# PORT.net
KiCad netlist of a schematic drawn in Altium Designer
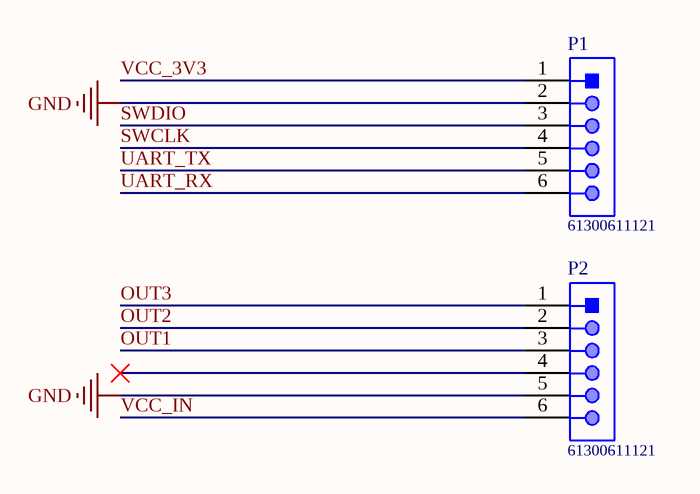
[diagram p0: PORT.SchDoc]

(export (version "E")
  (design (tool "Eeschema 10.0.6"))
  (components
    (comp (ref "P1")
      (value "61300611121")
      (footprint "61300611121")
      (description "THT Vertical Pin Header WR-PHD, Pitch 2.54 mm, Single Row, 6 pins")
      (fields (field (name "MANUFACTURER") "Wurth Elektronik") (field (name "PUBLISHER") "WurthElektronik"))
      (libsource (lib "Altium Content Vault") (part "WE-CN-1P-M-R6"))
    )
    (comp (ref "P2")
      (value "61300611121")
      (footprint "61300611121")
      (description "THT Vertical Pin Header WR-PHD, Pitch 2.54 mm, Single Row, 6 pins")
      (fields (field (name "MANUFACTURER") "Wurth Elektronik") (field (name "PUBLISHER") "WurthElektronik"))
      (libsource (lib "Altium Content Vault") (part "WE-CN-1P-M-R6"))
    )
  )
  (nets
    (net (code "1") (name "/OUT1") (class "Default")
      (node (ref "P2") (pin "3") (pinfunction "3_3") (pintype "passive"))
    )
    (net (code "2") (name "/OUT2") (class "Default")
      (node (ref "P2") (pin "2") (pinfunction "2_2") (pintype "passive"))
    )
    (net (code "3") (name "/OUT3") (class "Default")
      (node (ref "P2") (pin "1") (pinfunction "1_1") (pintype "passive"))
    )
    (net (code "4") (name "/SWCLK") (class "Default")
      (node (ref "P1") (pin "4") (pinfunction "4_4") (pintype "passive"))
    )
    (net (code "5") (name "/SWDIO") (class "Default")
      (node (ref "P1") (pin "3") (pinfunction "3_3") (pintype "passive"))
    )
    (net (code "6") (name "/UART_RX") (class "Default")
      (node (ref "P1") (pin "6") (pinfunction "6_6") (pintype "passive"))
    )
    (net (code "7") (name "/UART_TX") (class "Default")
      (node (ref "P1") (pin "5") (pinfunction "5_5") (pintype "passive"))
    )
    (net (code "8") (name "/VCC_3V3") (class "Default")
      (node (ref "P1") (pin "1") (pinfunction "1_1") (pintype "passive"))
    )
    (net (code "9") (name "/VCC_IN") (class "Default")
      (node (ref "P2") (pin "6") (pinfunction "6_6") (pintype "passive"))
    )
    (net (code "10") (name "GND") (class "Default")
      (node (ref "P1") (pin "2") (pinfunction "2_2") (pintype "passive"))
      (node (ref "P2") (pin "5") (pinfunction "5_5") (pintype "passive"))
    )
    (net (code "11") (name "unconnected-(P2-Pad4)") (class "Default")
      (node (ref "P2") (pin "4") (pinfunction "4_4") (pintype "passive+no_connect"))
    )
  )
)
